# 433brd.net
KiCad netlist of a schematic drawn in EAGLE
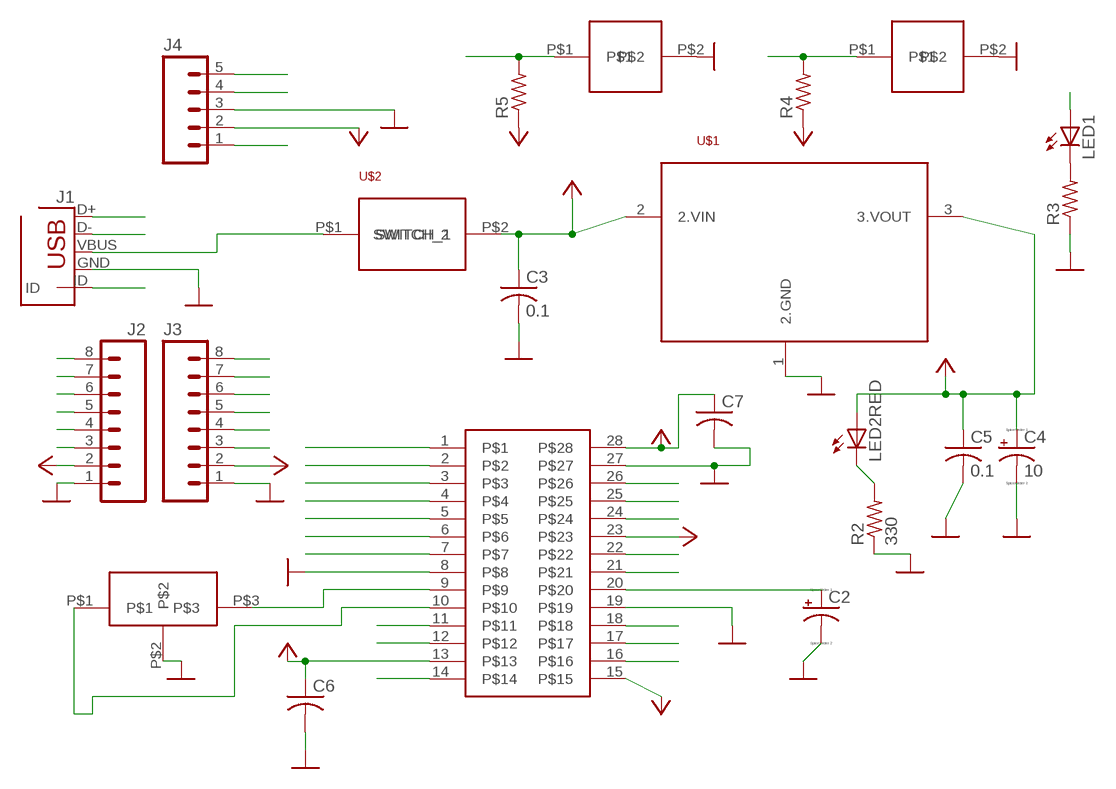
[diagram p0: schematic, sheet 1]

(export (version "E")
  (design (tool "Eeschema 10.0.6"))
  (components
    (comp (ref "C2")
      (value "CPOL-USE1.8-4")
      (footprint "eagle-import:E1,8-4")
      (libsource (lib "eagle-import") (part "CPOL-USE1.8-4"))
    )
    (comp (ref "C3")
      (value "0.1")
      (footprint "eagle-import:C025-024X044")
      (libsource (lib "eagle-import") (part "C-US025-024X044"))
    )
    (comp (ref "C4")
      (value "10")
      (footprint "eagle-import:E1,8-4")
      (libsource (lib "eagle-import") (part "CPOL-USE1.8-4"))
    )
    (comp (ref "C5")
      (value "0.1")
      (footprint "eagle-import:C025-024X044")
      (libsource (lib "eagle-import") (part "C-US025-024X044"))
    )
    (comp (ref "C6")
      (value "C-US025-024X044")
      (footprint "eagle-import:C025-024X044")
      (libsource (lib "eagle-import") (part "C-US025-024X044"))
    )
    (comp (ref "C7")
      (value "C-US025-024X044")
      (footprint "eagle-import:C025-024X044")
      (libsource (lib "eagle-import") (part "C-US025-024X044"))
    )
    (comp (ref "J1")
      (value "USB-MB-H")
      (footprint "eagle-import:USB-MB-H")
      (libsource (lib "eagle-import") (part "USB-MB-H"))
    )
    (comp (ref "J2")
      (value "M08")
      (footprint "eagle-import:1X08_ROUND")
      (libsource (lib "eagle-import") (part "M08"))
    )
    (comp (ref "J3")
      (value "M08")
      (footprint "eagle-import:1X08_ROUND")
      (libsource (lib "eagle-import") (part "M08"))
    )
    (comp (ref "J4")
      (value "M05PTH")
      (footprint "eagle-import:1X05")
      (libsource (lib "eagle-import") (part "M05PTH"))
    )
    (comp (ref "LED1")
      (value "LED3MM")
      (footprint "eagle-import:LED3MM")
      (libsource (lib "eagle-import") (part "LED3MM"))
    )
    (comp (ref "LED2RED")
      (value "LED3MM")
      (footprint "eagle-import:LED3MM")
      (libsource (lib "eagle-import") (part "LED3MM"))
    )
    (comp (ref "R2")
      (value "330")
      (footprint "eagle-import:0204_7")
      (libsource (lib "eagle-import") (part "R-US_0204/7"))
    )
    (comp (ref "R3")
      (value "R-US_0204/7")
      (footprint "eagle-import:0204_7")
      (libsource (lib "eagle-import") (part "R-US_0204/7"))
    )
    (comp (ref "R4")
      (value "R-US_0204/7")
      (footprint "eagle-import:0204_7")
      (libsource (lib "eagle-import") (part "R-US_0204/7"))
    )
    (comp (ref "R5")
      (value "R-US_0204/7")
      (footprint "eagle-import:0204_7")
      (libsource (lib "eagle-import") (part "R-US_0204/7"))
    )
    (comp (ref "U$1")
      (value "MCP1702")
      (footprint "eagle-import:TO92")
      (libsource (lib "eagle-import") (part "MCP1702"))
    )
    (comp (ref "U$2")
      (value "SLIDE_SWITCH")
      (footprint "eagle-import:SLIDE_SWITCH")
      (libsource (lib "eagle-import") (part "SLIDE_SWITCH"))
    )
    (comp (ref "U$3")
      (value "RESONATOR")
      (footprint "eagle-import:RESONATOR")
      (libsource (lib "eagle-import") (part "RESONATOR"))
    )
    (comp (ref "U$4")
      (value "DIPMOUNT")
      (footprint "eagle-import:DIL28-3")
      (libsource (lib "eagle-import") (part "DIPMOUNT"))
    )
    (comp (ref "U$5")
      (value "PUSHBUTTON")
      (footprint "eagle-import:PUSHBUTTON")
      (libsource (lib "eagle-import") (part "PUSHBUTTON"))
    )
    (comp (ref "U$6")
      (value "PUSHBUTTON")
      (footprint "eagle-import:PUSHBUTTON")
      (libsource (lib "eagle-import") (part "PUSHBUTTON"))
    )
  )
  (nets
    (net (code "1") (name "+3V3") (class "Default")
      (node (ref "C4") (pin "+") (pinfunction "+_+") (pintype "passive"))
      (node (ref "C5") (pin "1") (pinfunction "1_1") (pintype "passive"))
      (node (ref "C6") (pin "1") (pinfunction "1_1") (pintype "passive"))
      (node (ref "C7") (pin "1") (pinfunction "1_1") (pintype "passive"))
      (node (ref "J2") (pin "2") (pinfunction "2_2") (pintype "passive"))
      (node (ref "J4") (pin "2") (pinfunction "2_2") (pintype "passive"))
      (node (ref "LED2RED") (pin "A") (pinfunction "A_A") (pintype "passive"))
      (node (ref "R4") (pin "1") (pinfunction "1_1") (pintype "passive"))
      (node (ref "R5") (pin "1") (pinfunction "1_1") (pintype "passive"))
      (node (ref "U$1") (pin "3") (pinfunction "3.VOUT_3") (pintype "bidirectional"))
      (node (ref "U$4") (pin "13") (pinfunction "P$13_13") (pintype "bidirectional"))
      (node (ref "U$4") (pin "23") (pinfunction "P$23_23") (pintype "bidirectional"))
      (node (ref "U$4") (pin "28") (pinfunction "P$28_28") (pintype "bidirectional"))
    )
    (net (code "2") (name "+5V") (class "Default")
      (node (ref "C3") (pin "1") (pinfunction "1_1") (pintype "passive"))
      (node (ref "J3") (pin "2") (pinfunction "2_2") (pintype "passive"))
      (node (ref "U$1") (pin "2") (pinfunction "2.VIN_2") (pintype "bidirectional"))
      (node (ref "U$2") (pin "P$2") (pinfunction "SWITCH_2_P$2") (pintype "bidirectional"))
      (node (ref "U$4") (pin "15") (pinfunction "P$15_15") (pintype "bidirectional"))
    )
    (net (code "3") (name "/A0") (class "Default")
      (node (ref "J2") (pin "8") (pinfunction "8_8") (pintype "passive"))
      (node (ref "U$4") (pin "2") (pinfunction "P$2_2") (pintype "bidirectional"))
    )
    (net (code "4") (name "/A1") (class "Default")
      (node (ref "J2") (pin "7") (pinfunction "7_7") (pintype "passive"))
      (node (ref "U$4") (pin "3") (pinfunction "P$3_3") (pintype "bidirectional"))
    )
    (net (code "5") (name "/A4{slash}LED") (class "Default")
      (node (ref "J2") (pin "3") (pinfunction "3_3") (pintype "passive"))
      (node (ref "LED1") (pin "A") (pinfunction "A_A") (pintype "passive"))
      (node (ref "U$4") (pin "12") (pinfunction "P$12_12") (pintype "bidirectional"))
    )
    (net (code "6") (name "/B2") (class "Default")
      (node (ref "J2") (pin "6") (pinfunction "6_6") (pintype "passive"))
      (node (ref "U$4") (pin "6") (pinfunction "P$6_6") (pintype "bidirectional"))
    )
    (net (code "7") (name "/B3") (class "Default")
      (node (ref "J2") (pin "5") (pinfunction "5_5") (pintype "passive"))
      (node (ref "U$4") (pin "7") (pinfunction "P$7_7") (pintype "bidirectional"))
    )
    (net (code "8") (name "/B4{slash}USER") (class "Default")
      (node (ref "J2") (pin "4") (pinfunction "4_4") (pintype "passive"))
      (node (ref "R5") (pin "2") (pinfunction "2_2") (pintype "passive"))
      (node (ref "U$4") (pin "11") (pinfunction "P$11_11") (pintype "bidirectional"))
      (node (ref "U$5") (pin "P$1") (pinfunction "P$1_P$1") (pintype "bidirectional"))
    )
    (net (code "9") (name "/B7") (class "Default")
      (node (ref "J3") (pin "3") (pinfunction "3_3") (pintype "passive"))
      (node (ref "U$4") (pin "16") (pinfunction "P$16_16") (pintype "bidirectional"))
    )
    (net (code "10") (name "/B8") (class "Default")
      (node (ref "J3") (pin "4") (pinfunction "4_4") (pintype "passive"))
      (node (ref "U$4") (pin "17") (pinfunction "P$17_17") (pintype "bidirectional"))
    )
    (net (code "11") (name "/B9") (class "Default")
      (node (ref "J3") (pin "5") (pinfunction "5_5") (pintype "passive"))
      (node (ref "U$4") (pin "18") (pinfunction "P$18_18") (pintype "bidirectional"))
    )
    (net (code "12") (name "/B13") (class "Default")
      (node (ref "J3") (pin "6") (pinfunction "6_6") (pintype "passive"))
      (node (ref "U$4") (pin "24") (pinfunction "P$24_24") (pintype "bidirectional"))
    )
    (net (code "13") (name "/B14") (class "Default")
      (node (ref "J3") (pin "7") (pinfunction "7_7") (pintype "passive"))
      (node (ref "U$4") (pin "25") (pinfunction "P$25_25") (pintype "bidirectional"))
    )
    (net (code "14") (name "/B15") (class "Default")
      (node (ref "J3") (pin "8") (pinfunction "8_8") (pintype "passive"))
      (node (ref "U$4") (pin "26") (pinfunction "P$26_26") (pintype "bidirectional"))
    )
    (net (code "15") (name "/D+") (class "Default")
      (node (ref "J1") (pin "D+") (pinfunction "D+_D+") (pintype "bidirectional"))
      (node (ref "U$4") (pin "21") (pinfunction "P$21_21") (pintype "bidirectional"))
    )
    (net (code "16") (name "/D-") (class "Default")
      (node (ref "J1") (pin "D-") (pinfunction "D-_D-") (pintype "bidirectional"))
      (node (ref "U$4") (pin "22") (pinfunction "P$22_22") (pintype "bidirectional"))
    )
    (net (code "17") (name "/MCLR") (class "Default")
      (node (ref "J4") (pin "1") (pinfunction "1_1") (pintype "passive"))
      (node (ref "R4") (pin "2") (pinfunction "2_2") (pintype "passive"))
      (node (ref "U$4") (pin "1") (pinfunction "P$1_1") (pintype "bidirectional"))
      (node (ref "U$6") (pin "P$1") (pinfunction "P$1_P$1") (pintype "bidirectional"))
    )
    (net (code "18") (name "/PGC") (class "Default")
      (node (ref "J4") (pin "5") (pinfunction "5_5") (pintype "passive"))
      (node (ref "U$4") (pin "5") (pinfunction "P$5_5") (pintype "bidirectional"))
    )
    (net (code "19") (name "/PGD") (class "Default")
      (node (ref "J4") (pin "4") (pinfunction "4_4") (pintype "passive"))
      (node (ref "U$4") (pin "4") (pinfunction "P$4_4") (pintype "bidirectional"))
    )
    (net (code "20") (name "/USBID") (class "Default")
      (node (ref "J1") (pin "ID") (pinfunction "ID_ID") (pintype "bidirectional"))
      (node (ref "U$4") (pin "14") (pinfunction "P$14_14") (pintype "bidirectional"))
    )
    (net (code "21") (name "GND") (class "Default")
      (node (ref "C2") (pin "-") (pinfunction "-_-") (pintype "passive"))
      (node (ref "C3") (pin "2") (pinfunction "2_2") (pintype "passive"))
      (node (ref "C4") (pin "-") (pinfunction "-_-") (pintype "passive"))
      (node (ref "C5") (pin "2") (pinfunction "2_2") (pintype "passive"))
      (node (ref "C6") (pin "2") (pinfunction "2_2") (pintype "passive"))
      (node (ref "C7") (pin "2") (pinfunction "2_2") (pintype "passive"))
      (node (ref "J1") (pin "GND") (pinfunction "GND_GND") (pintype "bidirectional"))
      (node (ref "J2") (pin "1") (pinfunction "1_1") (pintype "passive"))
      (node (ref "J3") (pin "1") (pinfunction "1_1") (pintype "passive"))
      (node (ref "J4") (pin "3") (pinfunction "3_3") (pintype "passive"))
      (node (ref "R2") (pin "1") (pinfunction "1_1") (pintype "passive"))
      (node (ref "R3") (pin "1") (pinfunction "1_1") (pintype "passive"))
      (node (ref "U$1") (pin "1") (pinfunction "2.GND_1") (pintype "bidirectional"))
      (node (ref "U$3") (pin "P$2") (pinfunction "P$2_P$2") (pintype "bidirectional"))
      (node (ref "U$4") (pin "19") (pinfunction "P$19_19") (pintype "bidirectional"))
      (node (ref "U$4") (pin "27") (pinfunction "P$27_27") (pintype "bidirectional"))
      (node (ref "U$4") (pin "8") (pinfunction "P$8_8") (pintype "bidirectional"))
      (node (ref "U$5") (pin "P$2") (pinfunction "P$2_P$2") (pintype "bidirectional"))
      (node (ref "U$6") (pin "P$2") (pinfunction "P$2_P$2") (pintype "bidirectional"))
    )
    (net (code "22") (name "Net-(LED1-C)") (class "Default")
      (node (ref "LED1") (pin "K") (pinfunction "C_K") (pintype "passive"))
      (node (ref "R3") (pin "2") (pinfunction "2_2") (pintype "passive"))
    )
    (net (code "23") (name "Net-(LED2RED-C)") (class "Default")
      (node (ref "LED2RED") (pin "K") (pinfunction "C_K") (pintype "passive"))
      (node (ref "R2") (pin "2") (pinfunction "2_2") (pintype "passive"))
    )
    (net (code "24") (name "Net-(U$2-SWITCH_1)") (class "Default")
      (node (ref "J1") (pin "VBUS") (pinfunction "VBUS_VBUS") (pintype "bidirectional"))
      (node (ref "U$2") (pin "P$1") (pinfunction "SWITCH_1_P$1") (pintype "bidirectional"))
    )
    (net (code "25") (name "Net-(U$4-P$9)") (class "Default")
      (node (ref "U$3") (pin "P$3") (pinfunction "P$3_P$3") (pintype "bidirectional"))
      (node (ref "U$4") (pin "9") (pinfunction "P$9_9") (pintype "bidirectional"))
    )
    (net (code "26") (name "Net-(U$4-P$10)") (class "Default")
      (node (ref "U$3") (pin "P$1") (pinfunction "P$1_P$1") (pintype "bidirectional"))
      (node (ref "U$4") (pin "10") (pinfunction "P$10_10") (pintype "bidirectional"))
    )
    (net (code "27") (name "Net-(U$4-P$20)") (class "Default")
      (node (ref "C2") (pin "+") (pinfunction "+_+") (pintype "passive"))
      (node (ref "U$4") (pin "20") (pinfunction "P$20_20") (pintype "bidirectional"))
    )
  )
)
